# Option_lcd.net
KiCad netlist of a schematic drawn in Altium Designer
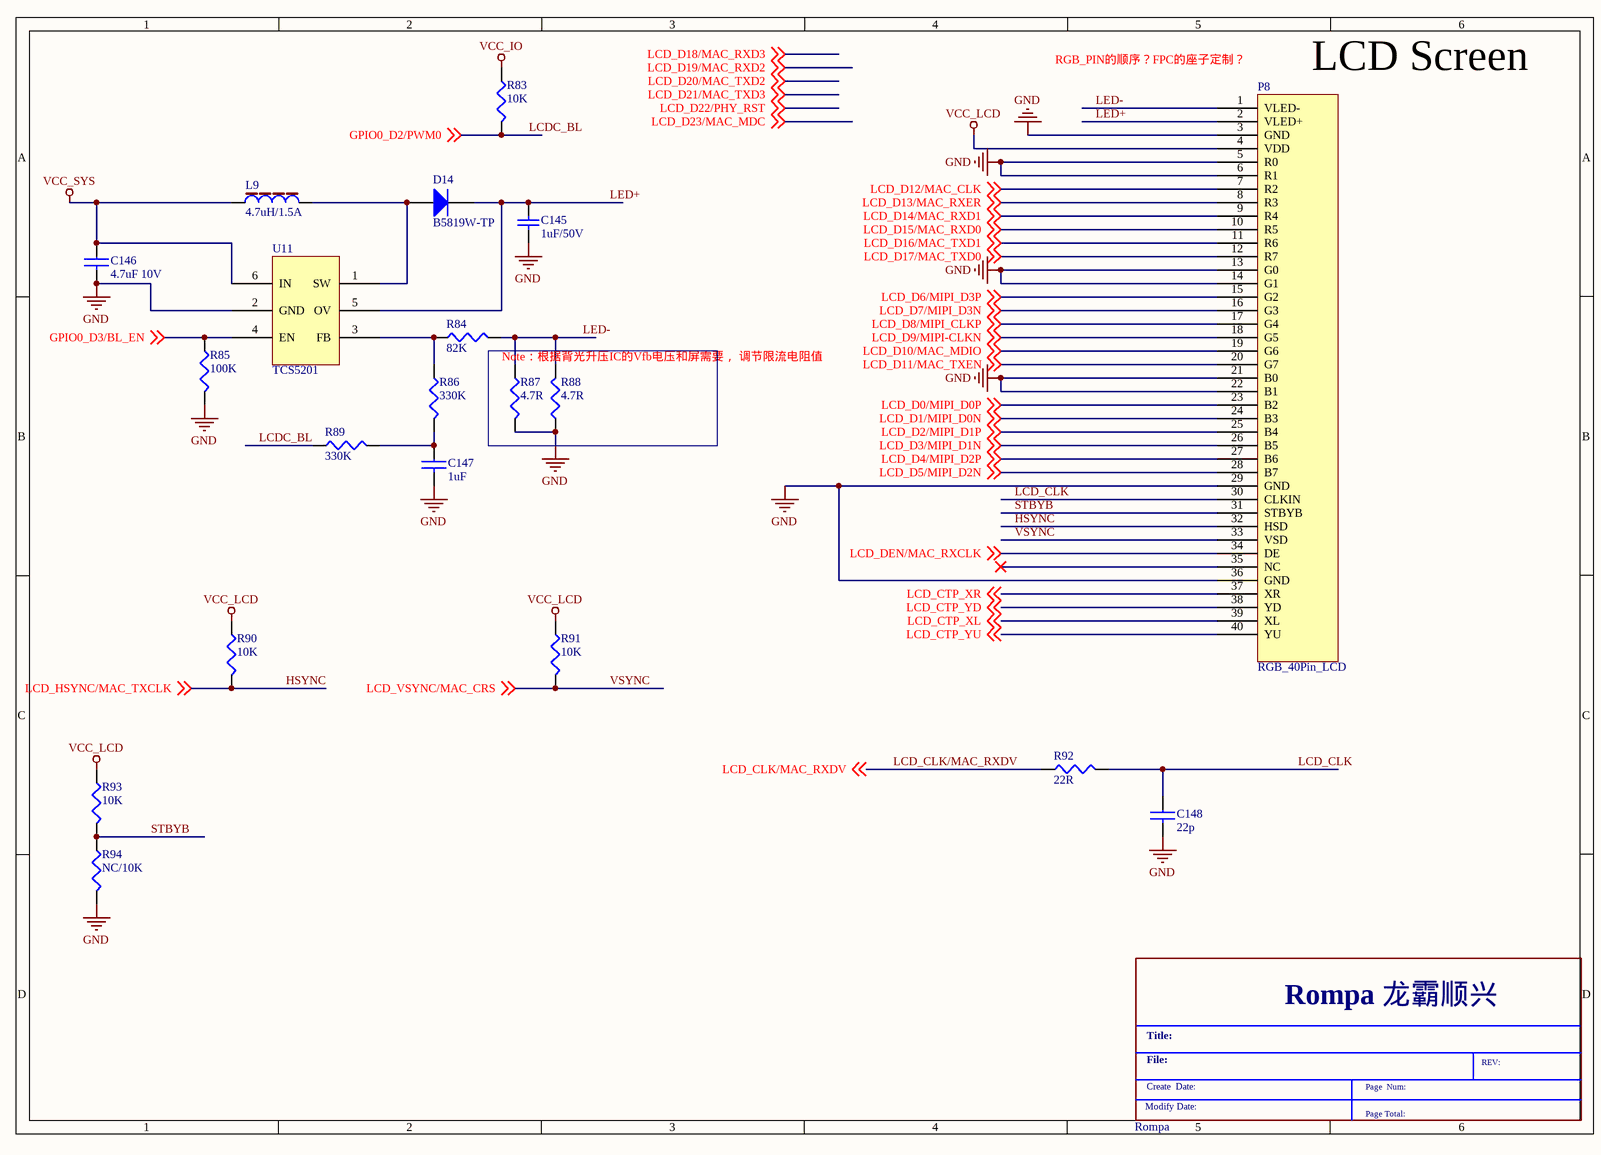
[diagram p0: Option_lcd.SchDoc]

(export (version "E")
  (design (tool "Eeschema 10.0.6"))
  (components
    (comp (ref "C145")
      (value "1uF/50V")
      (footprint "2012[0805]")
      (description "1uF/50V,")
      (fields (field (name "PUBLISHER") "Altium Limited"))
      (libsource (lib "Miscellaneous Devices") (part "Cap"))
    )
    (comp (ref "C146")
      (value "4.7uF 10V")
      (footprint "C0603")
      (libsource (lib "RK3128_BETA_V03_20151231_Library") (part "CAP NP_Dup1"))
    )
    (comp (ref "C147")
      (value "1uF")
      (footprint "C0805")
      (libsource (lib "RK3128_BETA_V03_20151231_Library") (part "CAP NP"))
    )
    (comp (ref "C148")
      (value "22p")
      (footprint "C0402")
      (libsource (lib "RK3128_BETA_V03_20151231_Library") (part "CAP NP"))
    )
    (comp (ref "D14")
      (value "B5819W-TP")
      (description "Micro Commercial Co ,  SOD-123")
      (fields (field (name "PUBLISHER") "Altium Limited"))
      (libsource (lib "Miscellaneous Devices") (part "Diode"))
    )
    (comp (ref "L9")
      (value "4.7uH/1.5A")
      (description "4.7uH/1.5A , IND_4x4")
      (libsource (lib "RK3128_BETA_V03_20151231_Library") (part "INDUCTOR_2"))
    )
    (comp (ref "P8")
      (value "RGB_40Pin_LCD")
      (description "FPC的规格：0.5mm间距， 40PING，Pitch2.0mm, 翻盖式 下接")
      (libsource (lib "iguide_custom") (part "RGB_40Pin_LCD"))
    )
    (comp (ref "R83")
      (value "10K")
      (footprint "R0402")
      (libsource (lib "RK3128_BETA_V03_20151231_Library") (part "RESISTOR"))
    )
    (comp (ref "R84")
      (value "82K")
      (footprint "R0402")
      (libsource (lib "RK3128_BETA_V03_20151231_Library") (part "RESISTOR"))
    )
    (comp (ref "R85")
      (value "100K")
      (footprint "R0402")
      (libsource (lib "RK3128_BETA_V03_20151231_Library") (part "RESISTOR"))
    )
    (comp (ref "R86")
      (value "330K")
      (footprint "R0402")
      (libsource (lib "RK3128_BETA_V03_20151231_Library") (part "RESISTOR"))
    )
    (comp (ref "R87")
      (value "4.7R")
      (footprint "1608[0603]")
      (libsource (lib "RK3128_BETA_V03_20151231_Library") (part "RESISTOR"))
    )
    (comp (ref "R88")
      (value "4.7R")
      (footprint "1608[0603]")
      (libsource (lib "RK3128_BETA_V03_20151231_Library") (part "RESISTOR"))
    )
    (comp (ref "R89")
      (value "330K")
      (footprint "R0402")
      (libsource (lib "RK3128_BETA_V03_20151231_Library") (part "RESISTOR"))
    )
    (comp (ref "R90")
      (value "10K")
      (footprint "R0402")
      (libsource (lib "RK3128_BETA_V03_20151231_Library") (part "RESISTOR"))
    )
    (comp (ref "R91")
      (value "10K")
      (footprint "R0402")
      (libsource (lib "RK3128_BETA_V03_20151231_Library") (part "RESISTOR"))
    )
    (comp (ref "R92")
      (value "22R")
      (footprint "R0402")
      (libsource (lib "RK3128_BETA_V03_20151231_Library") (part "RESISTOR"))
    )
    (comp (ref "R93")
      (value "10K")
      (footprint "R0402")
      (libsource (lib "RK3128_BETA_V03_20151231_Library") (part "RESISTOR"))
    )
    (comp (ref "R94")
      (value "NC/10K")
      (footprint "R0402")
      (libsource (lib "RK3128_BETA_V03_20151231_Library") (part "RESISTOR"))
    )
    (comp (ref "U11")
      (value "TCS5201")
      (description "LED升压模块, STO26")
      (libsource (lib "iguide_custom") (part "TCS5201"))
    )
  )
  (nets
    (net (code "1") (name "/LCD_CLK") (class "Default")
      (node (ref "C148") (pin "1") (pinfunction "1_1") (pintype "passive"))
      (node (ref "P8") (pin "30") (pinfunction "CLKIN_30") (pintype "passive"))
      (node (ref "R92") (pin "2") (pinfunction "2_2") (pintype "passive"))
    )
    (net (code "2") (name "/LED+") (class "Default")
      (node (ref "C145") (pin "2") (pinfunction "2_2") (pintype "passive"))
      (node (ref "D14") (pin "2") (pinfunction "K_2") (pintype "passive"))
      (node (ref "P8") (pin "2") (pinfunction "VLED+_2") (pintype "passive"))
      (node (ref "U11") (pin "5") (pinfunction "OV_5") (pintype "passive"))
    )
    (net (code "3") (name "/LED-") (class "Default")
      (node (ref "P8") (pin "1") (pinfunction "VLED-_1") (pintype "passive"))
      (node (ref "R84") (pin "2") (pinfunction "2_2") (pintype "passive"))
      (node (ref "R87") (pin "1") (pinfunction "1_1") (pintype "passive"))
      (node (ref "R88") (pin "2") (pinfunction "2_2") (pintype "passive"))
    )
    (net (code "4") (name "/STBYB") (class "Default")
      (node (ref "P8") (pin "31") (pinfunction "STBYB_31") (pintype "passive"))
      (node (ref "R93") (pin "2") (pinfunction "2_2") (pintype "passive"))
      (node (ref "R94") (pin "1") (pinfunction "1_1") (pintype "passive"))
    )
    (net (code "5") (name "GND") (class "Default")
      (node (ref "C145") (pin "1") (pinfunction "1_1") (pintype "passive"))
      (node (ref "C146") (pin "2") (pinfunction "2_2") (pintype "passive"))
      (node (ref "C147") (pin "2") (pinfunction "2_2") (pintype "passive"))
      (node (ref "C148") (pin "2") (pinfunction "2_2") (pintype "passive"))
      (node (ref "P8") (pin "13") (pinfunction "G0_13") (pintype "passive"))
      (node (ref "P8") (pin "14") (pinfunction "G1_14") (pintype "passive"))
      (node (ref "P8") (pin "21") (pinfunction "B0_21") (pintype "passive"))
      (node (ref "P8") (pin "22") (pinfunction "B1_22") (pintype "passive"))
      (node (ref "P8") (pin "29") (pinfunction "GND_29") (pintype "passive"))
      (node (ref "P8") (pin "3") (pinfunction "GND_3") (pintype "passive"))
      (node (ref "P8") (pin "36") (pinfunction "GND_36") (pintype "passive"))
      (node (ref "P8") (pin "5") (pinfunction "R0_5") (pintype "passive"))
      (node (ref "P8") (pin "6") (pinfunction "R1_6") (pintype "passive"))
      (node (ref "R85") (pin "2") (pinfunction "2_2") (pintype "passive"))
      (node (ref "R87") (pin "2") (pinfunction "2_2") (pintype "passive"))
      (node (ref "R88") (pin "1") (pinfunction "1_1") (pintype "passive"))
      (node (ref "R94") (pin "2") (pinfunction "2_2") (pintype "passive"))
      (node (ref "U11") (pin "2") (pinfunction "GND_2") (pintype "passive"))
    )
    (net (code "6") (name "GPIO0_D2{slash}PWM0") (class "Default")
      (node (ref "R83") (pin "2") (pinfunction "2_2") (pintype "passive"))
      (node (ref "R89") (pin "1") (pinfunction "1_1") (pintype "passive"))
    )
    (net (code "7") (name "GPIO0_D3{slash}BL_EN") (class "Default")
      (node (ref "R85") (pin "1") (pinfunction "1_1") (pintype "passive"))
      (node (ref "U11") (pin "4") (pinfunction "EN_4") (pintype "passive"))
    )
    (net (code "8") (name "LCD_CLK{slash}MAC_RXDV") (class "Default")
      (node (ref "R92") (pin "1") (pinfunction "1_1") (pintype "passive"))
    )
    (net (code "9") (name "LCD_CTP_XL") (class "Default")
      (node (ref "P8") (pin "39") (pinfunction "XL_39") (pintype "passive"))
    )
    (net (code "10") (name "LCD_CTP_XR") (class "Default")
      (node (ref "P8") (pin "37") (pinfunction "XR_37") (pintype "passive"))
    )
    (net (code "11") (name "LCD_CTP_YD") (class "Default")
      (node (ref "P8") (pin "38") (pinfunction "YD_38") (pintype "passive"))
    )
    (net (code "12") (name "LCD_CTP_YU") (class "Default")
      (node (ref "P8") (pin "40") (pinfunction "YU_40") (pintype "passive"))
    )
    (net (code "13") (name "LCD_D0{slash}MIPI_D0P") (class "Default")
      (node (ref "P8") (pin "23") (pinfunction "B2_23") (pintype "passive"))
    )
    (net (code "14") (name "LCD_D1{slash}MIPI_D0N") (class "Default")
      (node (ref "P8") (pin "24") (pinfunction "B3_24") (pintype "passive"))
    )
    (net (code "15") (name "LCD_D2{slash}MIPI_D1P") (class "Default")
      (node (ref "P8") (pin "25") (pinfunction "B4_25") (pintype "passive"))
    )
    (net (code "16") (name "LCD_D3{slash}MIPI_D1N") (class "Default")
      (node (ref "P8") (pin "26") (pinfunction "B5_26") (pintype "passive"))
    )
    (net (code "17") (name "LCD_D4{slash}MIPI_D2P") (class "Default")
      (node (ref "P8") (pin "27") (pinfunction "B6_27") (pintype "passive"))
    )
    (net (code "18") (name "LCD_D5{slash}MIPI_D2N") (class "Default")
      (node (ref "P8") (pin "28") (pinfunction "B7_28") (pintype "passive"))
    )
    (net (code "19") (name "LCD_D6{slash}MIPI_D3P") (class "Default")
      (node (ref "P8") (pin "15") (pinfunction "G2_15") (pintype "passive"))
    )
    (net (code "20") (name "LCD_D7{slash}MIPI_D3N") (class "Default")
      (node (ref "P8") (pin "16") (pinfunction "G3_16") (pintype "passive"))
    )
    (net (code "21") (name "LCD_D8{slash}MIPI_CLKP") (class "Default")
      (node (ref "P8") (pin "17") (pinfunction "G4_17") (pintype "passive"))
    )
    (net (code "22") (name "LCD_D9{slash}MIPI-CLKN") (class "Default")
      (node (ref "P8") (pin "18") (pinfunction "G5_18") (pintype "passive"))
    )
    (net (code "23") (name "LCD_D10{slash}MAC_MDIO") (class "Default")
      (node (ref "P8") (pin "19") (pinfunction "G6_19") (pintype "passive"))
    )
    (net (code "24") (name "LCD_D11{slash}MAC_TXEN") (class "Default")
      (node (ref "P8") (pin "20") (pinfunction "G7_20") (pintype "passive"))
    )
    (net (code "25") (name "LCD_D12{slash}MAC_CLK") (class "Default")
      (node (ref "P8") (pin "7") (pinfunction "R2_7") (pintype "passive"))
    )
    (net (code "26") (name "LCD_D13{slash}MAC_RXER") (class "Default")
      (node (ref "P8") (pin "8") (pinfunction "R3_8") (pintype "passive"))
    )
    (net (code "27") (name "LCD_D14{slash}MAC_RXD1") (class "Default")
      (node (ref "P8") (pin "9") (pinfunction "R4_9") (pintype "passive"))
    )
    (net (code "28") (name "LCD_D15{slash}MAC_RXD0") (class "Default")
      (node (ref "P8") (pin "10") (pinfunction "R5_10") (pintype "passive"))
    )
    (net (code "29") (name "LCD_D16{slash}MAC_TXD1") (class "Default")
      (node (ref "P8") (pin "11") (pinfunction "R6_11") (pintype "passive"))
    )
    (net (code "30") (name "LCD_D17{slash}MAC_TXD0") (class "Default")
      (node (ref "P8") (pin "12") (pinfunction "R7_12") (pintype "passive"))
    )
    (net (code "37") (name "LCD_DEN{slash}MAC_RXCLK") (class "Default")
      (node (ref "P8") (pin "34") (pinfunction "DE_34") (pintype "passive"))
    )
    (net (code "38") (name "LCD_HSYNC{slash}MAC_TXCLK") (class "Default")
      (node (ref "P8") (pin "32") (pinfunction "HSD_32") (pintype "passive"))
      (node (ref "R90") (pin "2") (pinfunction "2_2") (pintype "passive"))
    )
    (net (code "39") (name "LCD_VSYNC{slash}MAC_CRS") (class "Default")
      (node (ref "P8") (pin "33") (pinfunction "VSD_33") (pintype "passive"))
      (node (ref "R91") (pin "2") (pinfunction "2_2") (pintype "passive"))
    )
    (net (code "40") (name "Net-(C147-Pad1)") (class "Default")
      (node (ref "C147") (pin "1") (pinfunction "1_1") (pintype "passive"))
      (node (ref "R86") (pin "2") (pinfunction "2_2") (pintype "passive"))
      (node (ref "R89") (pin "2") (pinfunction "2_2") (pintype "passive"))
    )
    (net (code "41") (name "Net-(D14-A)") (class "Default")
      (node (ref "D14") (pin "1") (pinfunction "A_1") (pintype "passive"))
      (node (ref "L9") (pin "2") (pinfunction "2_2") (pintype "passive"))
      (node (ref "U11") (pin "1") (pinfunction "SW_1") (pintype "passive"))
    )
    (net (code "42") (name "Net-(U11-FB)") (class "Default")
      (node (ref "R84") (pin "1") (pinfunction "1_1") (pintype "passive"))
      (node (ref "R86") (pin "1") (pinfunction "1_1") (pintype "passive"))
      (node (ref "U11") (pin "3") (pinfunction "FB_3") (pintype "passive"))
    )
    (net (code "43") (name "VCC_IO") (class "Default")
      (node (ref "R83") (pin "1") (pinfunction "1_1") (pintype "passive"))
    )
    (net (code "44") (name "VCC_LCD") (class "Default")
      (node (ref "P8") (pin "4") (pinfunction "VDD_4") (pintype "passive"))
      (node (ref "R90") (pin "1") (pinfunction "1_1") (pintype "passive"))
      (node (ref "R91") (pin "1") (pinfunction "1_1") (pintype "passive"))
      (node (ref "R93") (pin "1") (pinfunction "1_1") (pintype "passive"))
    )
    (net (code "45") (name "VCC_SYS") (class "Default")
      (node (ref "C146") (pin "1") (pinfunction "1_1") (pintype "passive"))
      (node (ref "L9") (pin "1") (pinfunction "1_1") (pintype "passive"))
      (node (ref "U11") (pin "6") (pinfunction "IN_6") (pintype "passive"))
    )
    (net (code "46") (name "unconnected-(P8-NC-Pad35)") (class "Default")
      (node (ref "P8") (pin "35") (pinfunction "NC_35") (pintype "passive+no_connect"))
    )
  )
)
